# 2019_ESP01_Prog.net
KiCad netlist of a schematic drawn in Altium Designer
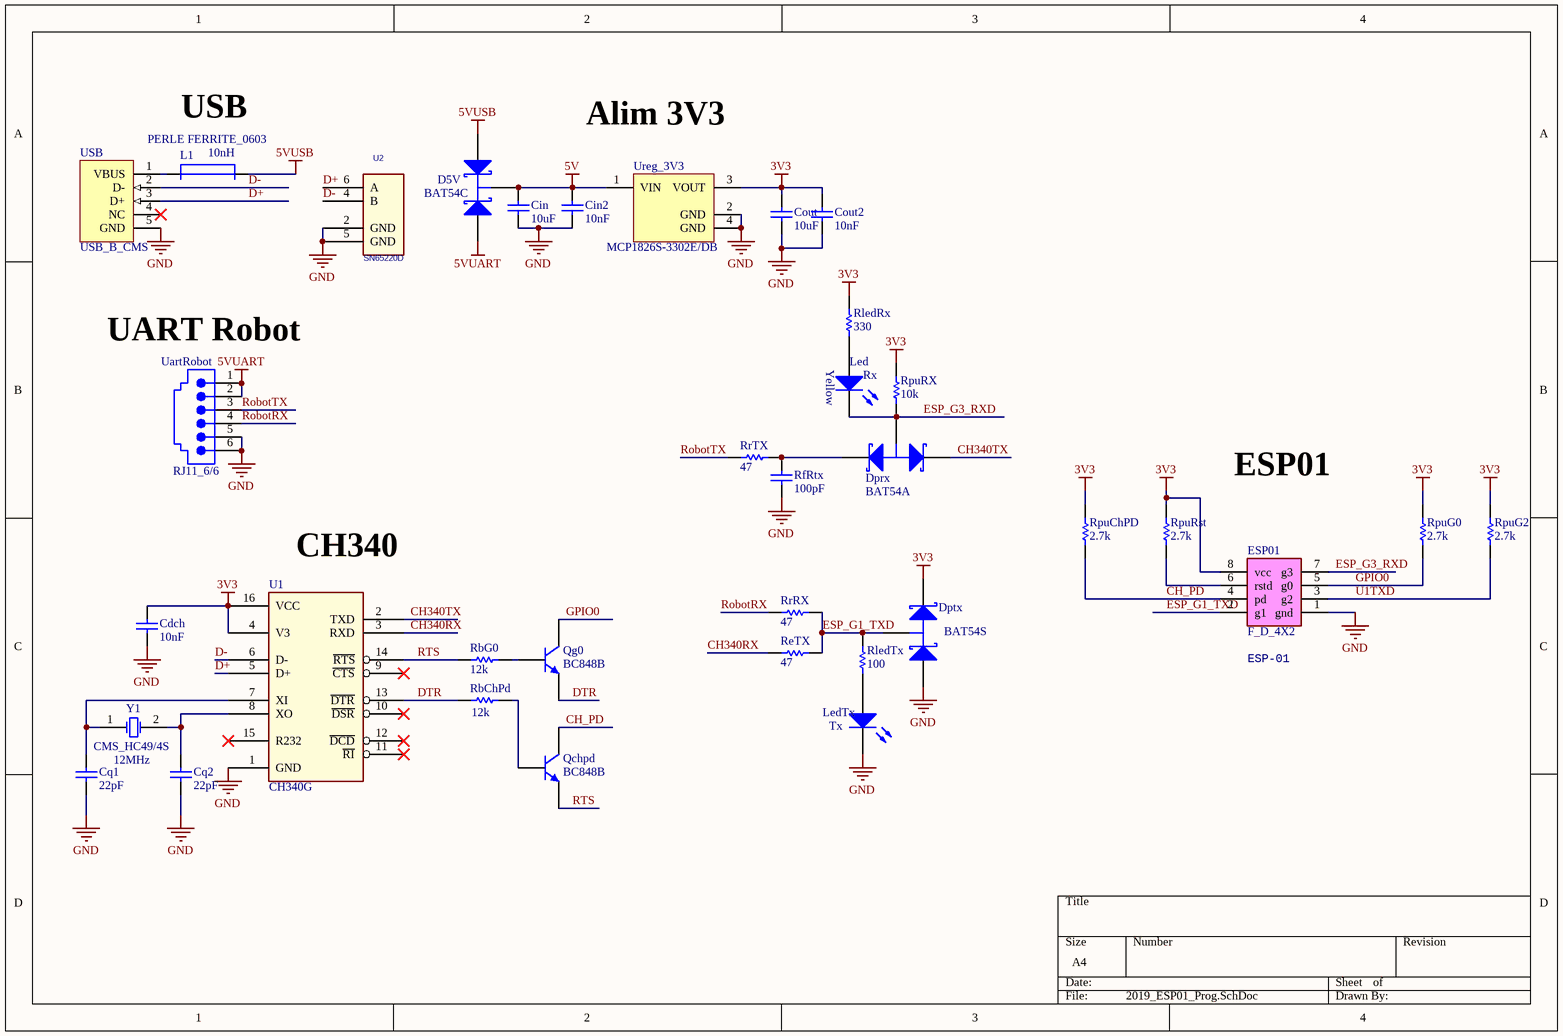
[diagram p0: 2019_ESP01_Prog.SchDoc]

(export (version "E")
  (design (tool "Eeschema 10.0.6"))
  (components
    (comp (ref "Cdch")
      (value "10nF")
      (footprint "C0805_N")
      (description "Capacitor")
      (fields (field (name "PUBLISHER") "Altium Limited"))
      (libsource (lib "DG_Condensateur") (part "Capacitor"))
    )
    (comp (ref "Cin")
      (value "10uF")
      (footprint "C1206_N")
      (description "Capacitor")
      (fields (field (name "PUBLISHER") "Altium Limited"))
      (libsource (lib "DG_Condensateur") (part "Capacitor"))
    )
    (comp (ref "Cin2")
      (value "10nF")
      (footprint "C0805_N")
      (description "Capacitor")
      (fields (field (name "PUBLISHER") "Altium Limited"))
      (libsource (lib "DG_Condensateur") (part "Capacitor"))
    )
    (comp (ref "Cout")
      (value "10uF")
      (footprint "C1206_N")
      (description "Capacitor")
      (fields (field (name "PUBLISHER") "Altium Limited"))
      (libsource (lib "DG_Condensateur") (part "Capacitor"))
    )
    (comp (ref "Cout2")
      (value "10nF")
      (footprint "C0805_N")
      (description "Capacitor")
      (fields (field (name "PUBLISHER") "Altium Limited"))
      (libsource (lib "DG_Condensateur") (part "Capacitor"))
    )
    (comp (ref "Cq1")
      (value "22pF")
      (footprint "C0805_N")
      (description "Capacitor")
      (fields (field (name "PUBLISHER") "Altium Limited"))
      (libsource (lib "DG_Condensateur") (part "Capacitor"))
    )
    (comp (ref "Cq2")
      (value "22pF")
      (footprint "C0805_N")
      (description "Capacitor")
      (fields (field (name "PUBLISHER") "Altium Limited"))
      (libsource (lib "DG_Condensateur") (part "Capacitor"))
    )
    (comp (ref "D5V")
      (value "BAT54C")
      (footprint "SOT23-3N")
      (description "DIODE SCHOTTKY DOUBLE")
      (fields (field (name "MANUFACTURER") "ZETEX"))
      (libsource (lib "_ROBOT") (part "Diode Shottky double BAT54C"))
    )
    (comp (ref "Dprx")
      (value "BAT54A")
      (footprint "SOT23-3N")
      (description "DIODE SCHOTTKY DOUBLE")
      (fields (field (name "MANUFACTURER") "ZETEX"))
      (libsource (lib "_ROBOT") (part "Diode Shottky double  BAT54A"))
    )
    (comp (ref "Dptx")
      (value "BAT54S")
      (footprint "SOT23-3N")
      (description "DIODE SCHOTTKY DOUBLE")
      (fields (field (name "MANUFACTURER") "ZETEX"))
      (libsource (lib "_ROBOT") (part "Diode Shottky double BAT54S"))
    )
    (comp (ref "ESP01")
      (value "BARRETTE_4 CONTACTS_2 RANGEES_FEMELLE_DROITE")
      (footprint "ESP01")
      (description "BARRETTE 4 CONTACTS 2 RANGEES FEMELLE DROITE")
      (fields (field (name "TYPE") "F_D_4X2"))
      (libsource (lib "connecteurs") (part "BARRETTE_4 CONTACTS_2 RANGEES_FEMELLE_DROITEE"))
    )
    (comp (ref "L1")
      (value "10nH")
      (footprint "INDUCTANCE_CMS_0603")
      (description "INDUCTANCE PERLE DE FERRITE_0603")
      (fields
        (field (name "TYPE") "PERLE FERRITE_0603")
        (field (name "Comment") "INDUCTANCE_PERLE_DE_FERRITE_0603")
      )
      (libsource (lib "composants passifs") (part "INDUCTANCE_PERLE_DE_FERRITE_0603"))
    )
    (comp (ref "Led")
      (value "Rx")
      (footprint "LED_0805")
      (description "Typical LED")
      (fields (field (name "PUBLISHER") "Altium Limited"))
      (libsource (lib "_ROBOT") (part "LED"))
    )
    (comp (ref "LedTx")
      (value "Tx")
      (footprint "LED_0805")
      (description "Typical LED")
      (fields (field (name "PUBLISHER") "Altium Limited"))
      (libsource (lib "_ROBOT") (part "LED"))
    )
    (comp (ref "Qchpd")
      (value "BC848B")
      (footprint "SOT23-3N")
      (description "NPN General-purpose Transistor")
      (fields (field (name "PUBLISHER") "Altium Limited"))
      (libsource (lib "Philips Discrete BJT - Low Power") (part "BC848B"))
    )
    (comp (ref "Qg0")
      (value "BC848B")
      (footprint "SOT23-3N")
      (description "NPN General-purpose Transistor")
      (fields (field (name "PUBLISHER") "Altium Limited"))
      (libsource (lib "Philips Discrete BJT - Low Power") (part "BC848B"))
    )
    (comp (ref "RbChPd")
      (value "12k")
      (footprint "R1206_N")
      (description "Resistor")
      (fields (field (name "PUBLISHER") "Altium Limited"))
      (libsource (lib "DG_Resistance") (part "Resistor"))
    )
    (comp (ref "RbG0")
      (value "12k")
      (footprint "R1206_N")
      (description "Resistor")
      (fields (field (name "PUBLISHER") "Altium Limited"))
      (libsource (lib "DG_Resistance") (part "Resistor"))
    )
    (comp (ref "ReTX")
      (value "47")
      (footprint "R1206_N")
      (description "Resistor")
      (fields (field (name "PUBLISHER") "Altium Limited"))
      (libsource (lib "DG_Resistance") (part "Resistor"))
    )
    (comp (ref "RfRtx")
      (value "100pF")
      (footprint "C0805_N")
      (description "Capacitor")
      (fields (field (name "PUBLISHER") "Altium Limited"))
      (libsource (lib "_ROBOT") (part "Condensateur"))
    )
    (comp (ref "RledRx")
      (value "330")
      (footprint "R1206_N")
      (description "Resistor")
      (fields (field (name "PUBLISHER") "Altium Limited"))
      (libsource (lib "_ROBOT") (part "Resistor"))
    )
    (comp (ref "RledTx")
      (value "100")
      (footprint "R1206_N")
      (description "Resistor")
      (fields (field (name "PUBLISHER") "Altium Limited"))
      (libsource (lib "_ROBOT") (part "Resistor"))
    )
    (comp (ref "RpuChPD")
      (value "2.7k")
      (footprint "R1206_N")
      (description "Resistor")
      (fields (field (name "PUBLISHER") "Altium Limited"))
      (libsource (lib "DG_Resistance") (part "Resistor"))
    )
    (comp (ref "RpuG0")
      (value "2.7k")
      (footprint "R1206_N")
      (description "Resistor")
      (fields (field (name "PUBLISHER") "Altium Limited"))
      (libsource (lib "DG_Resistance") (part "Resistor"))
    )
    (comp (ref "RpuG2")
      (value "2.7k")
      (footprint "R1206_N")
      (description "Resistor")
      (fields (field (name "PUBLISHER") "Altium Limited"))
      (libsource (lib "DG_Resistance") (part "Resistor"))
    )
    (comp (ref "RpuRst")
      (value "2.7k")
      (footprint "R1206_N")
      (description "Resistor")
      (fields (field (name "PUBLISHER") "Altium Limited"))
      (libsource (lib "DG_Resistance") (part "Resistor"))
    )
    (comp (ref "RpuRX")
      (value "10k")
      (footprint "R1206_N")
      (description "Resistor")
      (fields (field (name "PUBLISHER") "Altium Limited"))
      (libsource (lib "DG_Resistance") (part "Resistor"))
    )
    (comp (ref "RrRX")
      (value "47")
      (footprint "R1206_N")
      (description "Resistor")
      (fields (field (name "PUBLISHER") "Altium Limited"))
      (libsource (lib "DG_Resistance") (part "Resistor"))
    )
    (comp (ref "RrTX")
      (value "47")
      (footprint "R1206_N")
      (description "Resistor")
      (fields (field (name "PUBLISHER") "Altium Limited"))
      (libsource (lib "DG_Resistance") (part "Resistor"))
    )
    (comp (ref "U1")
      (value "CH340G")
      (footprint "SO16_N")
      (libsource (lib "CONTROLLER_Library") (part "CH340G"))
    )
    (comp (ref "U2")
      (value "SN65220D")
      (footprint "SOT26_PAS=0.95_LARG=3_LONG=3")
      (libsource (lib "*") (part "SN65220D"))
    )
    (comp (ref "UartRobot")
      (value "RJ11_6/6")
      (footprint "RJ11_6/6 - Wurth Half Shielded Tab Down WR-MJ")
      (description "Right Angle, Standard Profile, Offset Latch DECconnect, Flangeless PCB Jack")
      (fields (field (name "PUBLISHER") "Altium Limited"))
      (libsource (lib "Connecteur") (part "RJ11_6/6"))
    )
    (comp (ref "Ureg_3V3")
      (value "MCP1826S-3302E/DB")
      (footprint "SOT223-4N")
      (description "1000 mA, Low Voltage, Low Quiescent Current LDO Regulator, 3-Pin SOT-223, Extended Temperature")
      (fields (field (name "PUBLISHER") "Altium Limited"))
      (libsource (lib "Microchip Power Mgt Line Regulator") (part "MCP1826S-3302E/DB"))
    )
    (comp (ref "USB")
      (value "USB_B_CMS")
      (footprint "USB_MINI_B")
      (description "EMBASE USB CMS TYPE B")
      (fields (field (name "TYPE") "USB_B_CMS"))
      (libsource (lib "connecteurs") (part "USB_B_CMS"))
    )
    (comp (ref "Y1")
      (value "12MHz")
      (footprint "QUARTZ_CMS_HC49/4S")
      (description "QUARTZ CMS HC49/4S")
      (fields (field (name "TYPE") "CMS_HC49/4S") (field (name "Comment") "QUARTZ_CMS_HC49/4S"))
      (libsource (lib "composants passifs") (part "QUARTZ_CMS_HC49/4S"))
    )
  )
  (nets
    (net (code "1") (name "/CH340RX") (class "Default")
      (node (ref "ReTX") (pin "1") (pinfunction "1_1") (pintype "passive"))
      (node (ref "U1") (pin "3") (pinfunction "RXD_3") (pintype "passive"))
    )
    (net (code "2") (name "/CH340TX") (class "Default")
      (node (ref "Dprx") (pin "1") (pinfunction "K1_1") (pintype "passive"))
      (node (ref "U1") (pin "2") (pinfunction "TXD_2") (pintype "passive"))
    )
    (net (code "3") (name "/CH_PD") (class "Default")
      (node (ref "ESP01") (pin "4") (pinfunction "pd_4") (pintype "passive"))
      (node (ref "Qchpd") (pin "3") (pinfunction "C_3") (pintype "passive"))
      (node (ref "RpuChPD") (pin "1") (pinfunction "1_1") (pintype "passive"))
    )
    (net (code "4") (name "/D+") (class "Default")
      (node (ref "U1") (pin "5") (pinfunction "D+_5") (pintype "passive"))
      (node (ref "U2") (pin "6") (pinfunction "A_6") (pintype "passive"))
      (node (ref "USB") (pin "3") (pinfunction "D+_3") (pintype "input"))
    )
    (net (code "5") (name "/D-") (class "Default")
      (node (ref "U1") (pin "6") (pinfunction "D-_6") (pintype "passive"))
      (node (ref "U2") (pin "4") (pinfunction "B_4") (pintype "passive"))
      (node (ref "USB") (pin "2") (pinfunction "D-_2") (pintype "input"))
    )
    (net (code "6") (name "/DTR") (class "Default")
      (node (ref "Qg0") (pin "2") (pinfunction "E_2") (pintype "passive"))
      (node (ref "RbChPd") (pin "2") (pinfunction "2_2") (pintype "passive"))
      (node (ref "U1") (pin "13") (pinfunction "~{DTR}_13") (pintype "passive"))
    )
    (net (code "7") (name "/ESP_G1_TXD") (class "Default")
      (node (ref "Dptx") (pin "3") (pinfunction "C_3") (pintype "passive"))
      (node (ref "ESP01") (pin "2") (pinfunction "g1_2") (pintype "passive"))
      (node (ref "ReTX") (pin "2") (pinfunction "2_2") (pintype "passive"))
      (node (ref "RledTx") (pin "1") (pinfunction "1_1") (pintype "passive"))
      (node (ref "RrRX") (pin "2") (pinfunction "2_2") (pintype "passive"))
    )
    (net (code "8") (name "/ESP_G3_RXD") (class "Default")
      (node (ref "Dprx") (pin "3") (pinfunction "A_3") (pintype "passive"))
      (node (ref "ESP01") (pin "7") (pinfunction "g3_7") (pintype "passive"))
      (node (ref "Led") (pin "2") (pinfunction "K_2") (pintype "passive"))
      (node (ref "RpuRX") (pin "1") (pinfunction "1_1") (pintype "passive"))
    )
    (net (code "9") (name "/GPIO0") (class "Default")
      (node (ref "ESP01") (pin "5") (pinfunction "g0_5") (pintype "passive"))
      (node (ref "Qg0") (pin "3") (pinfunction "C_3") (pintype "passive"))
      (node (ref "RpuG0") (pin "1") (pinfunction "1_1") (pintype "passive"))
    )
    (net (code "10") (name "/RTS") (class "Default")
      (node (ref "Qchpd") (pin "2") (pinfunction "E_2") (pintype "passive"))
      (node (ref "RbG0") (pin "2") (pinfunction "2_2") (pintype "passive"))
      (node (ref "U1") (pin "14") (pinfunction "~{RTS}_14") (pintype "passive"))
    )
    (net (code "11") (name "/RobotRX") (class "Default")
      (node (ref "RrRX") (pin "1") (pinfunction "1_1") (pintype "passive"))
      (node (ref "UartRobot") (pin "4") (pinfunction "4_4") (pintype "passive"))
    )
    (net (code "12") (name "/RobotTX") (class "Default")
      (node (ref "RrTX") (pin "1") (pinfunction "1_1") (pintype "passive"))
      (node (ref "UartRobot") (pin "3") (pinfunction "3_3") (pintype "passive"))
    )
    (net (code "13") (name "/U1TXD") (class "Default")
      (node (ref "ESP01") (pin "3") (pinfunction "g2_3") (pintype "passive"))
      (node (ref "RpuG2") (pin "1") (pinfunction "1_1") (pintype "passive"))
    )
    (net (code "14") (name "3V3") (class "Default")
      (node (ref "Cdch") (pin "2") (pinfunction "2_2") (pintype "passive"))
      (node (ref "Cout") (pin "2") (pinfunction "2_2") (pintype "passive"))
      (node (ref "Cout2") (pin "2") (pinfunction "2_2") (pintype "passive"))
      (node (ref "Dptx") (pin "2") (pinfunction "K_2") (pintype "passive"))
      (node (ref "ESP01") (pin "8") (pinfunction "vcc_8") (pintype "passive"))
      (node (ref "RledRx") (pin "1") (pinfunction "1_1") (pintype "passive"))
      (node (ref "RpuChPD") (pin "2") (pinfunction "2_2") (pintype "passive"))
      (node (ref "RpuG0") (pin "2") (pinfunction "2_2") (pintype "passive"))
      (node (ref "RpuG2") (pin "2") (pinfunction "2_2") (pintype "passive"))
      (node (ref "RpuRX") (pin "2") (pinfunction "2_2") (pintype "passive"))
      (node (ref "RpuRst") (pin "2") (pinfunction "2_2") (pintype "passive"))
      (node (ref "U1") (pin "16") (pinfunction "VCC_16") (pintype "passive"))
      (node (ref "U1") (pin "4") (pinfunction "V3_4") (pintype "passive"))
      (node (ref "Ureg_3V3") (pin "3") (pinfunction "VOUT_3") (pintype "power_in"))
    )
    (net (code "15") (name "5V") (class "Default")
      (node (ref "Cin") (pin "2") (pinfunction "2_2") (pintype "passive"))
      (node (ref "Cin2") (pin "2") (pinfunction "2_2") (pintype "passive"))
      (node (ref "D5V") (pin "3") (pinfunction "K_3") (pintype "passive"))
      (node (ref "Ureg_3V3") (pin "1") (pinfunction "VIN_1") (pintype "power_in"))
    )
    (net (code "16") (name "5VUART") (class "Default")
      (node (ref "D5V") (pin "2") (pinfunction "A2_2") (pintype "passive"))
      (node (ref "UartRobot") (pin "1") (pinfunction "1_1") (pintype "passive"))
      (node (ref "UartRobot") (pin "2") (pinfunction "2_2") (pintype "passive"))
    )
    (net (code "17") (name "5VUSB") (class "Default")
      (node (ref "D5V") (pin "1") (pinfunction "A1_1") (pintype "passive"))
      (node (ref "L1") (pin "2") (pinfunction "2_2") (pintype "passive"))
    )
    (net (code "18") (name "GND") (class "Default")
      (node (ref "Cdch") (pin "1") (pinfunction "1_1") (pintype "passive"))
      (node (ref "Cin") (pin "1") (pinfunction "1_1") (pintype "passive"))
      (node (ref "Cin2") (pin "1") (pinfunction "1_1") (pintype "passive"))
      (node (ref "Cout") (pin "1") (pinfunction "1_1") (pintype "passive"))
      (node (ref "Cout2") (pin "1") (pinfunction "1_1") (pintype "passive"))
      (node (ref "Cq1") (pin "1") (pinfunction "1_1") (pintype "passive"))
      (node (ref "Cq2") (pin "1") (pinfunction "1_1") (pintype "passive"))
      (node (ref "Dptx") (pin "1") (pinfunction "A_1") (pintype "passive"))
      (node (ref "ESP01") (pin "1") (pinfunction "gnd_1") (pintype "passive"))
      (node (ref "LedTx") (pin "2") (pinfunction "K_2") (pintype "passive"))
      (node (ref "RfRtx") (pin "1") (pinfunction "1_1") (pintype "passive"))
      (node (ref "U1") (pin "1") (pinfunction "GND_1") (pintype "passive"))
      (node (ref "U2") (pin "2") (pinfunction "GND_2") (pintype "passive"))
      (node (ref "U2") (pin "5") (pinfunction "GND_5") (pintype "passive"))
      (node (ref "USB") (pin "5") (pinfunction "GND_5") (pintype "power_in"))
      (node (ref "UartRobot") (pin "5") (pinfunction "5_5") (pintype "passive"))
      (node (ref "UartRobot") (pin "6") (pinfunction "6_6") (pintype "passive"))
      (node (ref "Ureg_3V3") (pin "2") (pinfunction "GND_2") (pintype "power_in"))
      (node (ref "Ureg_3V3") (pin "4") (pinfunction "GND_4") (pintype "power_in"))
    )
    (net (code "19") (name "Net-(Dprx-K2)") (class "Default")
      (node (ref "Dprx") (pin "2") (pinfunction "K2_2") (pintype "passive"))
      (node (ref "RfRtx") (pin "2") (pinfunction "2_2") (pintype "passive"))
      (node (ref "RrTX") (pin "2") (pinfunction "2_2") (pintype "passive"))
    )
    (net (code "20") (name "Net-(ESP01-rstd)") (class "Default")
      (node (ref "ESP01") (pin "6") (pinfunction "rstd_6") (pintype "passive"))
      (node (ref "RpuRst") (pin "1") (pinfunction "1_1") (pintype "passive"))
    )
    (net (code "21") (name "Net-(Led-A)") (class "Default")
      (node (ref "Led") (pin "1") (pinfunction "A_1") (pintype "passive"))
      (node (ref "RledRx") (pin "2") (pinfunction "2_2") (pintype "passive"))
    )
    (net (code "22") (name "Net-(LedTx-A)") (class "Default")
      (node (ref "LedTx") (pin "1") (pinfunction "A_1") (pintype "passive"))
      (node (ref "RledTx") (pin "2") (pinfunction "2_2") (pintype "passive"))
    )
    (net (code "23") (name "Net-(Qchpd-B)") (class "Default")
      (node (ref "Qchpd") (pin "1") (pinfunction "B_1") (pintype "passive"))
      (node (ref "RbChPd") (pin "1") (pinfunction "1_1") (pintype "passive"))
    )
    (net (code "24") (name "Net-(Qg0-B)") (class "Default")
      (node (ref "Qg0") (pin "1") (pinfunction "B_1") (pintype "passive"))
      (node (ref "RbG0") (pin "1") (pinfunction "1_1") (pintype "passive"))
    )
    (net (code "25") (name "Net-(U1-XI)") (class "Default")
      (node (ref "Cq1") (pin "2") (pinfunction "2_2") (pintype "passive"))
      (node (ref "U1") (pin "7") (pinfunction "XI_7") (pintype "passive"))
      (node (ref "Y1") (pin "1") (pinfunction "OSC1_1") (pintype "passive"))
    )
    (net (code "26") (name "Net-(U1-XO)") (class "Default")
      (node (ref "Cq2") (pin "2") (pinfunction "2_2") (pintype "passive"))
      (node (ref "U1") (pin "8") (pinfunction "XO_8") (pintype "passive"))
      (node (ref "Y1") (pin "2") (pinfunction "OSC2_2") (pintype "passive"))
    )
    (net (code "27") (name "Net-(USB-VBUS)") (class "Default")
      (node (ref "L1") (pin "1") (pinfunction "1_1") (pintype "passive"))
      (node (ref "USB") (pin "1") (pinfunction "VBUS_1") (pintype "power_in"))
    )
    (net (code "28") (name "unconnected-(U1-R232-Pad15)") (class "Default")
      (node (ref "U1") (pin "15") (pinfunction "R232_15") (pintype "passive+no_connect"))
    )
    (net (code "29") (name "unconnected-(U1-~{CTS}-Pad9)") (class "Default")
      (node (ref "U1") (pin "9") (pinfunction "~{CTS}_9") (pintype "passive+no_connect"))
    )
    (net (code "30") (name "unconnected-(U1-~{DCD}-Pad12)") (class "Default")
      (node (ref "U1") (pin "12") (pinfunction "~{DCD}_12") (pintype "passive+no_connect"))
    )
    (net (code "31") (name "unconnected-(U1-~{DSR}-Pad10)") (class "Default")
      (node (ref "U1") (pin "10") (pinfunction "~{DSR}_10") (pintype "passive+no_connect"))
    )
    (net (code "32") (name "unconnected-(U1-~{RI}-Pad11)") (class "Default")
      (node (ref "U1") (pin "11") (pinfunction "~{RI}_11") (pintype "passive+no_connect"))
    )
    (net (code "33") (name "unconnected-(USB-NC-Pad4)") (class "Default")
      (node (ref "USB") (pin "4") (pinfunction "NC_4") (pintype "power_in+no_connect"))
    )
  )
)
